# WaterLevelSensor.net
KiCad netlist of a schematic drawn in EAGLE
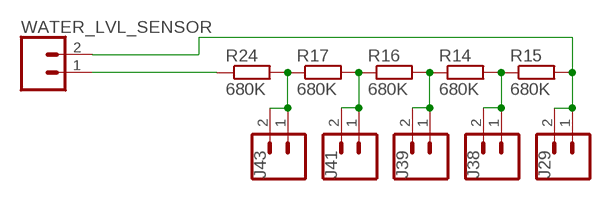
[diagram p0: schematic, sheet 1]

(export (version "E")
  (design (tool "Eeschema 10.0.6"))
  (components
    (comp (ref "J29")
      (value "CONN_02_NO_SILK")
      (footprint "eagle-import:1X02_NO_SILK")
      (libsource (lib "eagle-import") (part "CONN_02_NO_SILK"))
    )
    (comp (ref "J38")
      (value "CONN_02_NO_SILK")
      (footprint "eagle-import:1X02_NO_SILK")
      (libsource (lib "eagle-import") (part "CONN_02_NO_SILK"))
    )
    (comp (ref "J39")
      (value "CONN_02_NO_SILK")
      (footprint "eagle-import:1X02_NO_SILK")
      (libsource (lib "eagle-import") (part "CONN_02_NO_SILK"))
    )
    (comp (ref "J41")
      (value "CONN_02_NO_SILK")
      (footprint "eagle-import:1X02_NO_SILK")
      (libsource (lib "eagle-import") (part "CONN_02_NO_SILK"))
    )
    (comp (ref "J43")
      (value "CONN_02_NO_SILK")
      (footprint "eagle-import:1X02_NO_SILK")
      (libsource (lib "eagle-import") (part "CONN_02_NO_SILK"))
    )
    (comp (ref "R14")
      (value "680K")
      (footprint "eagle-import:R0805")
      (libsource (lib "eagle-import") (part "R-EU_R0805"))
    )
    (comp (ref "R15")
      (value "680K")
      (footprint "eagle-import:R0805")
      (libsource (lib "eagle-import") (part "R-EU_R0805"))
    )
    (comp (ref "R16")
      (value "680K")
      (footprint "eagle-import:R0805")
      (libsource (lib "eagle-import") (part "R-EU_R0805"))
    )
    (comp (ref "R17")
      (value "680K")
      (footprint "eagle-import:R0805")
      (libsource (lib "eagle-import") (part "R-EU_R0805"))
    )
    (comp (ref "R24")
      (value "680K")
      (footprint "eagle-import:R0805")
      (libsource (lib "eagle-import") (part "R-EU_R0805"))
    )
    (comp (ref "WATER_LVL_SENSOR")
      (value "CONN_02_NO_SILKPADS")
      (footprint "eagle-import:1X02_PADS")
      (libsource (lib "eagle-import") (part "CONN_02_NO_SILKPADS"))
    )
  )
  (nets
    (net (code "1") (name "Net-(J29-Pad1)") (class "Default")
      (node (ref "J29") (pin "1") (pinfunction "1_1") (pintype "passive"))
      (node (ref "J29") (pin "2") (pinfunction "2_2") (pintype "passive"))
      (node (ref "R15") (pin "2") (pinfunction "2_2") (pintype "passive"))
      (node (ref "WATER_LVL_SENSOR") (pin "2") (pinfunction "2_2") (pintype "passive"))
    )
    (net (code "2") (name "Net-(J38-Pad1)") (class "Default")
      (node (ref "J38") (pin "1") (pinfunction "1_1") (pintype "passive"))
      (node (ref "J38") (pin "2") (pinfunction "2_2") (pintype "passive"))
      (node (ref "R14") (pin "2") (pinfunction "2_2") (pintype "passive"))
      (node (ref "R15") (pin "1") (pinfunction "1_1") (pintype "passive"))
    )
    (net (code "3") (name "Net-(J39-Pad1)") (class "Default")
      (node (ref "J39") (pin "1") (pinfunction "1_1") (pintype "passive"))
      (node (ref "J39") (pin "2") (pinfunction "2_2") (pintype "passive"))
      (node (ref "R14") (pin "1") (pinfunction "1_1") (pintype "passive"))
      (node (ref "R16") (pin "2") (pinfunction "2_2") (pintype "passive"))
    )
    (net (code "4") (name "Net-(J41-Pad1)") (class "Default")
      (node (ref "J41") (pin "1") (pinfunction "1_1") (pintype "passive"))
      (node (ref "J41") (pin "2") (pinfunction "2_2") (pintype "passive"))
      (node (ref "R16") (pin "1") (pinfunction "1_1") (pintype "passive"))
      (node (ref "R17") (pin "2") (pinfunction "2_2") (pintype "passive"))
    )
    (net (code "5") (name "Net-(J43-Pad1)") (class "Default")
      (node (ref "J43") (pin "1") (pinfunction "1_1") (pintype "passive"))
      (node (ref "J43") (pin "2") (pinfunction "2_2") (pintype "passive"))
      (node (ref "R17") (pin "1") (pinfunction "1_1") (pintype "passive"))
      (node (ref "R24") (pin "2") (pinfunction "2_2") (pintype "passive"))
    )
    (net (code "6") (name "Net-(R24-Pad1)") (class "Default")
      (node (ref "R24") (pin "1") (pinfunction "1_1") (pintype "passive"))
      (node (ref "WATER_LVL_SENSOR") (pin "1") (pinfunction "1_1") (pintype "passive"))
    )
  )
)
